# Ultrasonic.net
KiCad netlist of a schematic drawn in EAGLE
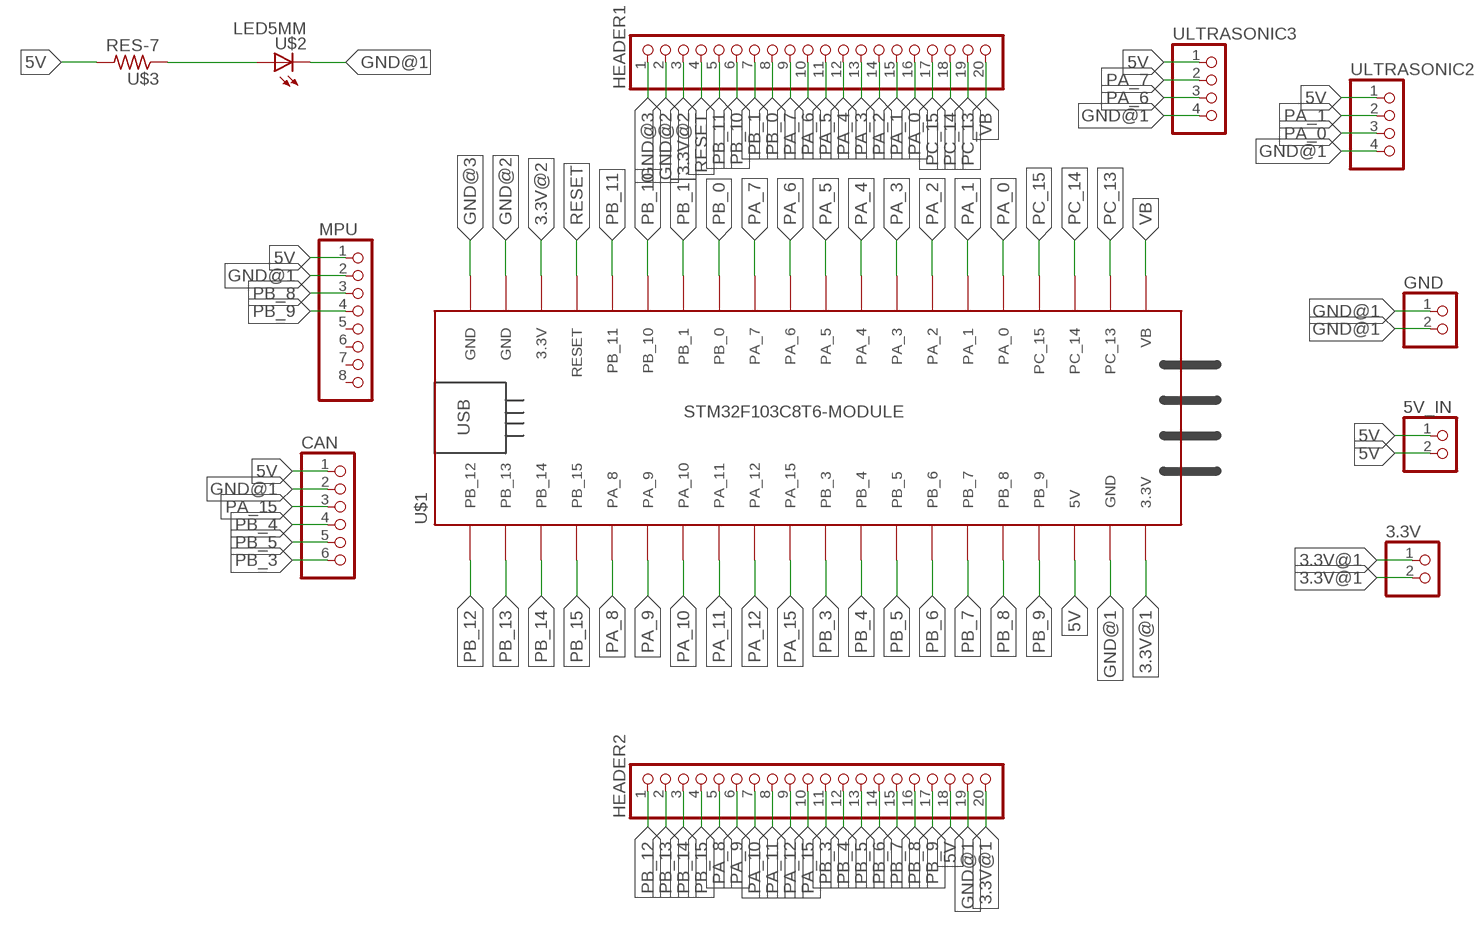
[diagram p0: schematic, sheet 1]

(export (version "E")
  (design (tool "Eeschema 10.0.6"))
  (components
    (comp (ref "3.3V")
      (value "PINHD-2_DATA")
      (footprint "eagle-import:1X02_DATA")
      (libsource (lib "eagle-import") (part "PINHD-2_DATA"))
    )
    (comp (ref "5V_IN")
      (value "PINHD-2_DATA")
      (footprint "eagle-import:1X02_DATA")
      (libsource (lib "eagle-import") (part "PINHD-2_DATA"))
    )
    (comp (ref "CAN")
      (value "PINHD-6_DATA")
      (footprint "eagle-import:1X06_DATA")
      (libsource (lib "eagle-import") (part "PINHD-6_DATA"))
    )
    (comp (ref "GND")
      (value "PINHD-2_DATA")
      (footprint "eagle-import:1X02_DATA")
      (libsource (lib "eagle-import") (part "PINHD-2_DATA"))
    )
    (comp (ref "HEADER1")
      (value "PINHD-1X20")
      (footprint "eagle-import:1X20")
      (libsource (lib "eagle-import") (part "PINHD-1X20"))
    )
    (comp (ref "HEADER2")
      (value "PINHD-1X20")
      (footprint "eagle-import:1X20")
      (libsource (lib "eagle-import") (part "PINHD-1X20"))
    )
    (comp (ref "MPU")
      (value "PINHD-1X8")
      (footprint "eagle-import:1X08")
      (libsource (lib "eagle-import") (part "PINHD-1X8"))
    )
    (comp (ref "U$1")
      (value "STM32F103C8T6-MODULE")
      (footprint "eagle-import:STM32F103C8T6-MODULE")
      (libsource (lib "eagle-import") (part "STM32F103C8T6-MODULE"))
    )
    (comp (ref "U$2")
      (value "LED5MM")
      (footprint "eagle-import:LED5MM")
      (libsource (lib "eagle-import") (part "LED5MM"))
    )
    (comp (ref "U$3")
      (value "RES-7")
      (footprint "eagle-import:0204_7")
      (libsource (lib "eagle-import") (part "RES-7"))
    )
    (comp (ref "ULTRASONIC2")
      (value "PINHD-4_DATA")
      (footprint "eagle-import:1X04_DATA")
      (libsource (lib "eagle-import") (part "PINHD-4_DATA"))
    )
    (comp (ref "ULTRASONIC3")
      (value "PINHD-4_DATA")
      (footprint "eagle-import:1X04_DATA")
      (libsource (lib "eagle-import") (part "PINHD-4_DATA"))
    )
  )
  (nets
    (net (code "1") (name "3.3V@1") (class "Default")
      (node (ref "3.3V") (pin "1") (pinfunction "1_1") (pintype "passive"))
      (node (ref "3.3V") (pin "2") (pinfunction "2_2") (pintype "passive"))
      (node (ref "HEADER2") (pin "20") (pinfunction "20_20") (pintype "passive"))
      (node (ref "U$1") (pin "3.3V_1") (pinfunction "3.3V_3.3V_1") (pintype "bidirectional"))
    )
    (net (code "2") (name "3.3V@2") (class "Default")
      (node (ref "HEADER1") (pin "3") (pinfunction "3_3") (pintype "passive"))
      (node (ref "U$1") (pin "3.3V_2") (pinfunction "3.3V_3.3V_2") (pintype "bidirectional"))
    )
    (net (code "3") (name "5V") (class "Default")
      (node (ref "5V_IN") (pin "1") (pinfunction "1_1") (pintype "passive"))
      (node (ref "5V_IN") (pin "2") (pinfunction "2_2") (pintype "passive"))
      (node (ref "CAN") (pin "1") (pinfunction "1_1") (pintype "passive"))
      (node (ref "HEADER2") (pin "18") (pinfunction "18_18") (pintype "passive"))
      (node (ref "MPU") (pin "1") (pinfunction "1_1") (pintype "passive"))
      (node (ref "U$1") (pin "5V") (pinfunction "5V_5V") (pintype "bidirectional"))
      (node (ref "U$3") (pin "2") (pinfunction "2_2") (pintype "passive"))
      (node (ref "ULTRASONIC2") (pin "1") (pinfunction "1_1") (pintype "passive"))
      (node (ref "ULTRASONIC3") (pin "1") (pinfunction "1_1") (pintype "passive"))
    )
    (net (code "4") (name "GND@1") (class "Default")
      (node (ref "CAN") (pin "2") (pinfunction "2_2") (pintype "passive"))
      (node (ref "GND") (pin "1") (pinfunction "1_1") (pintype "passive"))
      (node (ref "GND") (pin "2") (pinfunction "2_2") (pintype "passive"))
      (node (ref "HEADER2") (pin "19") (pinfunction "19_19") (pintype "passive"))
      (node (ref "MPU") (pin "2") (pinfunction "2_2") (pintype "passive"))
      (node (ref "U$1") (pin "GND_1") (pinfunction "GND_GND_1") (pintype "bidirectional"))
      (node (ref "U$2") (pin "K") (pinfunction "C_K") (pintype "passive"))
      (node (ref "ULTRASONIC2") (pin "4") (pinfunction "4_4") (pintype "passive"))
      (node (ref "ULTRASONIC3") (pin "4") (pinfunction "4_4") (pintype "passive"))
    )
    (net (code "5") (name "GND@2") (class "Default")
      (node (ref "HEADER1") (pin "2") (pinfunction "2_2") (pintype "passive"))
      (node (ref "U$1") (pin "GND_2") (pinfunction "GND_GND_2") (pintype "bidirectional"))
    )
    (net (code "6") (name "GND@3") (class "Default")
      (node (ref "HEADER1") (pin "1") (pinfunction "1_1") (pintype "passive"))
      (node (ref "U$1") (pin "GND_3") (pinfunction "GND_GND_3") (pintype "power_in"))
    )
    (net (code "7") (name "Net-(U$2-PadA)") (class "Default")
      (node (ref "U$2") (pin "A") (pinfunction "A_A") (pintype "passive"))
      (node (ref "U$3") (pin "1") (pinfunction "1_1") (pintype "passive"))
    )
    (net (code "8") (name "PA_0") (class "Default")
      (node (ref "HEADER1") (pin "16") (pinfunction "16_16") (pintype "passive"))
      (node (ref "U$1") (pin "PA_0") (pinfunction "PA_0_PA_0") (pintype "bidirectional"))
      (node (ref "ULTRASONIC2") (pin "3") (pinfunction "3_3") (pintype "passive"))
    )
    (net (code "9") (name "PA_1") (class "Default")
      (node (ref "HEADER1") (pin "15") (pinfunction "15_15") (pintype "passive"))
      (node (ref "U$1") (pin "PA_1") (pinfunction "PA_1_PA_1") (pintype "bidirectional"))
      (node (ref "ULTRASONIC2") (pin "2") (pinfunction "2_2") (pintype "passive"))
    )
    (net (code "10") (name "PA_2") (class "Default")
      (node (ref "HEADER1") (pin "14") (pinfunction "14_14") (pintype "passive"))
      (node (ref "U$1") (pin "PA_2") (pinfunction "PA_2_PA_2") (pintype "bidirectional"))
    )
    (net (code "11") (name "PA_3") (class "Default")
      (node (ref "HEADER1") (pin "13") (pinfunction "13_13") (pintype "passive"))
      (node (ref "U$1") (pin "PA_3") (pinfunction "PA_3_PA_3") (pintype "bidirectional"))
    )
    (net (code "12") (name "PA_4") (class "Default")
      (node (ref "HEADER1") (pin "12") (pinfunction "12_12") (pintype "passive"))
      (node (ref "U$1") (pin "PA_4") (pinfunction "PA_4_PA_4") (pintype "bidirectional"))
    )
    (net (code "13") (name "PA_5") (class "Default")
      (node (ref "HEADER1") (pin "11") (pinfunction "11_11") (pintype "passive"))
      (node (ref "U$1") (pin "PA_5") (pinfunction "PA_5_PA_5") (pintype "bidirectional"))
    )
    (net (code "14") (name "PA_6") (class "Default")
      (node (ref "HEADER1") (pin "10") (pinfunction "10_10") (pintype "passive"))
      (node (ref "U$1") (pin "PA_6") (pinfunction "PA_6_PA_6") (pintype "bidirectional"))
      (node (ref "ULTRASONIC3") (pin "3") (pinfunction "3_3") (pintype "passive"))
    )
    (net (code "15") (name "PA_7") (class "Default")
      (node (ref "HEADER1") (pin "9") (pinfunction "9_9") (pintype "passive"))
      (node (ref "U$1") (pin "PA_7") (pinfunction "PA_7_PA_7") (pintype "bidirectional"))
      (node (ref "ULTRASONIC3") (pin "2") (pinfunction "2_2") (pintype "passive"))
    )
    (net (code "16") (name "PA_8") (class "Default")
      (node (ref "HEADER2") (pin "5") (pinfunction "5_5") (pintype "passive"))
      (node (ref "U$1") (pin "PA_8") (pinfunction "PA_8_PA_8") (pintype "bidirectional"))
    )
    (net (code "17") (name "PA_9") (class "Default")
      (node (ref "HEADER2") (pin "6") (pinfunction "6_6") (pintype "passive"))
      (node (ref "U$1") (pin "PA_9") (pinfunction "PA_9_PA_9") (pintype "bidirectional"))
    )
    (net (code "18") (name "PA_10") (class "Default")
      (node (ref "HEADER2") (pin "7") (pinfunction "7_7") (pintype "passive"))
      (node (ref "U$1") (pin "PA_10") (pinfunction "PA_10_PA_10") (pintype "bidirectional"))
    )
    (net (code "19") (name "PA_11") (class "Default")
      (node (ref "HEADER2") (pin "8") (pinfunction "8_8") (pintype "passive"))
      (node (ref "U$1") (pin "PA_11") (pinfunction "PA_11_PA_11") (pintype "bidirectional"))
    )
    (net (code "20") (name "PA_12") (class "Default")
      (node (ref "HEADER2") (pin "9") (pinfunction "9_9") (pintype "passive"))
      (node (ref "U$1") (pin "PA_12") (pinfunction "PA_12_PA_12") (pintype "bidirectional"))
    )
    (net (code "21") (name "PA_15") (class "Default")
      (node (ref "CAN") (pin "3") (pinfunction "3_3") (pintype "passive"))
      (node (ref "HEADER2") (pin "10") (pinfunction "10_10") (pintype "passive"))
      (node (ref "U$1") (pin "PA_15") (pinfunction "PA_15_PA_15") (pintype "bidirectional"))
    )
    (net (code "22") (name "PB_0") (class "Default")
      (node (ref "HEADER1") (pin "8") (pinfunction "8_8") (pintype "passive"))
      (node (ref "U$1") (pin "PB_0") (pinfunction "PB_0_PB_0") (pintype "bidirectional"))
    )
    (net (code "23") (name "PB_1") (class "Default")
      (node (ref "HEADER1") (pin "7") (pinfunction "7_7") (pintype "passive"))
      (node (ref "U$1") (pin "PB_1") (pinfunction "PB_1_PB_1") (pintype "bidirectional"))
    )
    (net (code "24") (name "PB_3") (class "Default")
      (node (ref "CAN") (pin "6") (pinfunction "6_6") (pintype "passive"))
      (node (ref "HEADER2") (pin "11") (pinfunction "11_11") (pintype "passive"))
      (node (ref "U$1") (pin "PB_3") (pinfunction "PB_3_PB_3") (pintype "bidirectional"))
    )
    (net (code "25") (name "PB_4") (class "Default")
      (node (ref "CAN") (pin "4") (pinfunction "4_4") (pintype "passive"))
      (node (ref "HEADER2") (pin "12") (pinfunction "12_12") (pintype "passive"))
      (node (ref "U$1") (pin "PB_4") (pinfunction "PB_4_PB_4") (pintype "bidirectional"))
    )
    (net (code "26") (name "PB_5") (class "Default")
      (node (ref "CAN") (pin "5") (pinfunction "5_5") (pintype "passive"))
      (node (ref "HEADER2") (pin "13") (pinfunction "13_13") (pintype "passive"))
      (node (ref "U$1") (pin "PB_5") (pinfunction "PB_5_PB_5") (pintype "bidirectional"))
    )
    (net (code "27") (name "PB_6") (class "Default")
      (node (ref "HEADER2") (pin "14") (pinfunction "14_14") (pintype "passive"))
      (node (ref "U$1") (pin "PB_6") (pinfunction "PB_6_PB_6") (pintype "bidirectional"))
    )
    (net (code "28") (name "PB_7") (class "Default")
      (node (ref "HEADER2") (pin "15") (pinfunction "15_15") (pintype "passive"))
      (node (ref "U$1") (pin "PB_7") (pinfunction "PB_7_PB_7") (pintype "bidirectional"))
    )
    (net (code "29") (name "PB_8") (class "Default")
      (node (ref "HEADER2") (pin "16") (pinfunction "16_16") (pintype "passive"))
      (node (ref "MPU") (pin "3") (pinfunction "3_3") (pintype "passive"))
      (node (ref "U$1") (pin "PB_8") (pinfunction "PB_8_PB_8") (pintype "bidirectional"))
    )
    (net (code "30") (name "PB_9") (class "Default")
      (node (ref "HEADER2") (pin "17") (pinfunction "17_17") (pintype "passive"))
      (node (ref "MPU") (pin "4") (pinfunction "4_4") (pintype "passive"))
      (node (ref "U$1") (pin "PB_9") (pinfunction "PB_9_PB_9") (pintype "bidirectional"))
    )
    (net (code "31") (name "PB_10") (class "Default")
      (node (ref "HEADER1") (pin "6") (pinfunction "6_6") (pintype "passive"))
      (node (ref "U$1") (pin "PB_10") (pinfunction "PB_10_PB_10") (pintype "bidirectional"))
    )
    (net (code "32") (name "PB_11") (class "Default")
      (node (ref "HEADER1") (pin "5") (pinfunction "5_5") (pintype "passive"))
      (node (ref "U$1") (pin "PB_11") (pinfunction "PB_11_PB_11") (pintype "bidirectional"))
    )
    (net (code "33") (name "PB_12") (class "Default")
      (node (ref "HEADER2") (pin "1") (pinfunction "1_1") (pintype "passive"))
      (node (ref "U$1") (pin "PB_12") (pinfunction "PB_12_PB_12") (pintype "bidirectional"))
    )
    (net (code "34") (name "PB_13") (class "Default")
      (node (ref "HEADER2") (pin "2") (pinfunction "2_2") (pintype "passive"))
      (node (ref "U$1") (pin "PB_13") (pinfunction "PB_13_PB_13") (pintype "bidirectional"))
    )
    (net (code "35") (name "PB_14") (class "Default")
      (node (ref "HEADER2") (pin "3") (pinfunction "3_3") (pintype "passive"))
      (node (ref "U$1") (pin "PB_14") (pinfunction "PB_14_PB_14") (pintype "bidirectional"))
    )
    (net (code "36") (name "PB_15") (class "Default")
      (node (ref "HEADER2") (pin "4") (pinfunction "4_4") (pintype "passive"))
      (node (ref "U$1") (pin "PB_15") (pinfunction "PB_15_PB_15") (pintype "bidirectional"))
    )
    (net (code "37") (name "PC_13") (class "Default")
      (node (ref "HEADER1") (pin "19") (pinfunction "19_19") (pintype "passive"))
      (node (ref "U$1") (pin "PC_13") (pinfunction "PC_13_PC_13") (pintype "bidirectional"))
    )
    (net (code "38") (name "PC_14") (class "Default")
      (node (ref "HEADER1") (pin "18") (pinfunction "18_18") (pintype "passive"))
      (node (ref "U$1") (pin "PC_14") (pinfunction "PC_14_PC_14") (pintype "bidirectional"))
    )
    (net (code "39") (name "PC_15") (class "Default")
      (node (ref "HEADER1") (pin "17") (pinfunction "17_17") (pintype "passive"))
      (node (ref "U$1") (pin "PC_15") (pinfunction "PC_15_PC_15") (pintype "bidirectional"))
    )
    (net (code "40") (name "RESET") (class "Default")
      (node (ref "HEADER1") (pin "4") (pinfunction "4_4") (pintype "passive"))
      (node (ref "U$1") (pin "RESET") (pinfunction "RESET_RESET") (pintype "bidirectional"))
    )
    (net (code "41") (name "VB") (class "Default")
      (node (ref "HEADER1") (pin "20") (pinfunction "20_20") (pintype "passive"))
      (node (ref "U$1") (pin "VB") (pinfunction "VB_VB") (pintype "bidirectional"))
    )
    (net (code "42") (name "unconnected-(MPU-Pad5)") (class "Default")
      (node (ref "MPU") (pin "5") (pinfunction "5_5") (pintype "passive"))
    )
    (net (code "43") (name "unconnected-(MPU-Pad6)") (class "Default")
      (node (ref "MPU") (pin "6") (pinfunction "6_6") (pintype "passive"))
    )
    (net (code "44") (name "unconnected-(MPU-Pad7)") (class "Default")
      (node (ref "MPU") (pin "7") (pinfunction "7_7") (pintype "passive"))
    )
    (net (code "45") (name "unconnected-(MPU-Pad8)") (class "Default")
      (node (ref "MPU") (pin "8") (pinfunction "8_8") (pintype "passive"))
    )
  )
)
